# design.net
KiCad netlist of a schematic drawn in Altium Designer
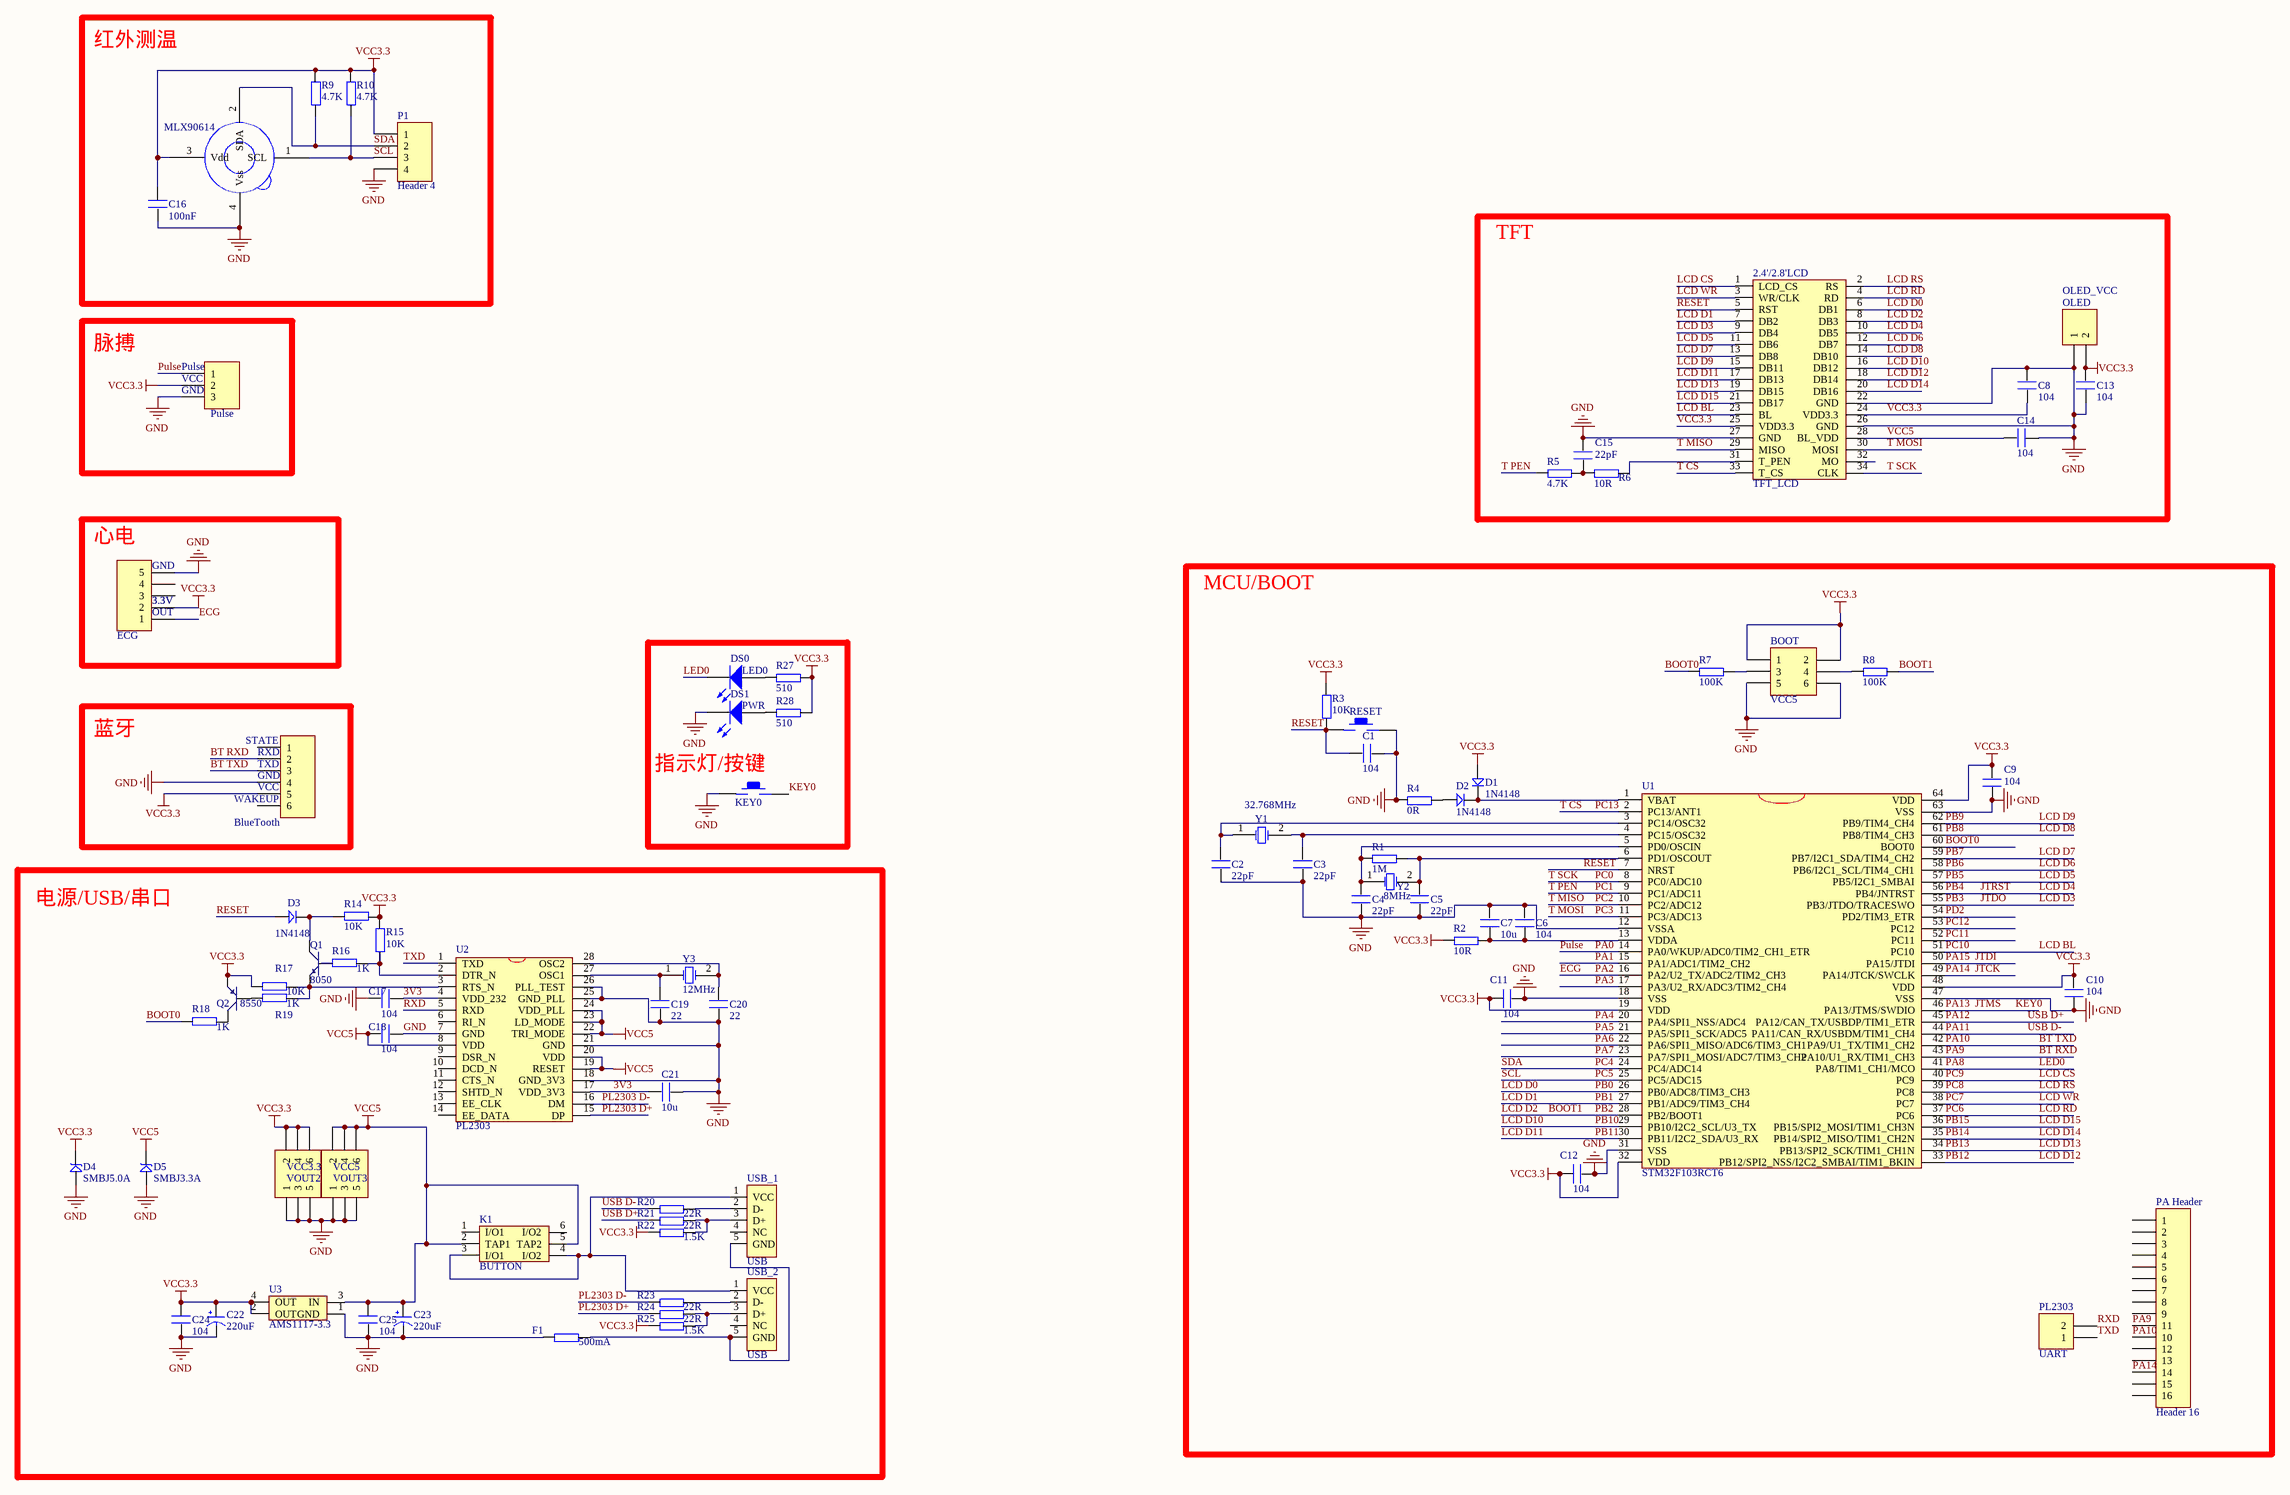
[diagram p0: 远程医疗.SchDoc]

(export (version "E")
  (design (tool "Eeschema 10.0.6"))
  (components
    (comp (ref "2.4'/2.8'LCD")
      (value "TFT_LCD")
      (footprint "DB2*17")
      (libsource (lib "MiniSTM32 V2.0封装库") (part "TFT_LCD"))
    )
    (comp (ref "BlueTooth")
      (value "BlueTooth")
      (footprint "BlueTooth")
      (libsource (lib "my Integrated lib ") (part "BlueTooth"))
    )
    (comp (ref "BOOT")
      (value "VCC5")
      (footprint "HDR2X3")
      (description "Header, 3-Pin, Dual row")
      (fields (field (name "PUBLISHER") "Altium Limited"))
      (libsource (lib "") (part "Header 3X2_1"))
    )
    (comp (ref "C1") (value "104") (footprint "0603P") (libsource (lib "MiniSTM32 V2.0封装库") (part "C")))
    (comp (ref "C2") (value "22pF") (footprint "0603P") (libsource (lib "MiniSTM32 V2.0封装库") (part "C")))
    (comp (ref "C3") (value "22pF") (footprint "0603P") (libsource (lib "MiniSTM32 V2.0封装库") (part "C")))
    (comp (ref "C4") (value "22pF") (footprint "0603P") (libsource (lib "MiniSTM32 V2.0封装库") (part "C")))
    (comp (ref "C5") (value "22pF") (footprint "0603P") (libsource (lib "MiniSTM32 V2.0封装库") (part "C")))
    (comp (ref "C6") (value "104") (footprint "0603P") (libsource (lib "MiniSTM32 V2.0封装库") (part "C")))
    (comp (ref "C7") (value "10u") (footprint "0603P") (libsource (lib "MiniSTM32 V2.0封装库") (part "C")))
    (comp (ref "C8") (value "104") (footprint "0603P") (libsource (lib "MiniSTM32 V2.0封装库") (part "C")))
    (comp (ref "C9") (value "104") (footprint "0603P") (libsource (lib "MiniSTM32 V2.0封装库") (part "C")))
    (comp (ref "C10") (value "104") (footprint "0603P") (libsource (lib "MiniSTM32 V2.0封装库") (part "C")))
    (comp (ref "C11") (value "104") (footprint "0603P") (libsource (lib "MiniSTM32 V2.0封装库") (part "C")))
    (comp (ref "C12") (value "104") (footprint "0603P") (libsource (lib "MiniSTM32 V2.0封装库") (part "C")))
    (comp (ref "C13") (value "104") (footprint "0603P") (libsource (lib "MiniSTM32 V2.0封装库") (part "C")))
    (comp (ref "C14") (value "104") (footprint "0603P") (libsource (lib "MiniSTM32 V2.0封装库") (part "C")))
    (comp (ref "C15") (value "22pF") (footprint "0603P") (libsource (lib "MiniSTM32 V2.0封装库") (part "C")))
    (comp (ref "C16") (value "100nF") (footprint "0603P") (libsource (lib "MiniSTM32 V2.0封装库") (part "C")))
    (comp (ref "C17") (value "104") (footprint "0603P") (libsource (lib "MiniSTM32 V2.0封装库") (part "C")))
    (comp (ref "C18") (value "104") (footprint "0603P") (libsource (lib "MiniSTM32 V2.0封装库") (part "C")))
    (comp (ref "C19") (value "22") (footprint "0603P") (libsource (lib "MiniSTM32 V2.0封装库") (part "C")))
    (comp (ref "C20") (value "22") (footprint "0603P") (libsource (lib "MiniSTM32 V2.0封装库") (part "C")))
    (comp (ref "C21") (value "10u") (footprint "0603P") (libsource (lib "MiniSTM32 V2.0封装库") (part "C")))
    (comp (ref "C22")
      (value "220uF")
      (footprint "CC6.56.5")
      (libsource (lib "MiniSTM32 V2.0封装库") (part "CAP"))
    )
    (comp (ref "C23")
      (value "220uF")
      (footprint "CC6.56.5")
      (libsource (lib "MiniSTM32 V2.0封装库") (part "CAP"))
    )
    (comp (ref "C24") (value "104") (footprint "0603P") (libsource (lib "MiniSTM32 V2.0封装库") (part "C")))
    (comp (ref "C25") (value "104") (footprint "0603P") (libsource (lib "MiniSTM32 V2.0封装库") (part "C")))
    (comp (ref "D1")
      (value "1N4148")
      (footprint "DIODE_SOP")
      (libsource (lib "MiniSTM32 V2.0封装库") (part "D"))
    )
    (comp (ref "D2")
      (value "1N4148")
      (footprint "DIODE_SOP")
      (libsource (lib "MiniSTM32 V2.0封装库") (part "D"))
    )
    (comp (ref "D3")
      (value "1N4148")
      (footprint "DIODE_SOP")
      (libsource (lib "MiniSTM32 V2.0封装库") (part "D"))
    )
    (comp (ref "D4")
      (value "SMBJ5.0A")
      (footprint "SMBJ")
      (description "TVS")
      (libsource (lib "MiniSTM32 V2.0封装库") (part "SMBJ"))
    )
    (comp (ref "D5")
      (value "SMBJ3.3A")
      (footprint "SMBJ")
      (description "TVS")
      (libsource (lib "MiniSTM32 V2.0封装库") (part "SMBJ"))
    )
    (comp (ref "DS0")
      (value "LED0")
      (footprint "SMDLED")
      (description "Typical RED, GREEN, YELLOW, AMBER GaAs LED")
      (fields (field (name "PUBLISHER") "Altium Limited"))
      (libsource (lib "MiniSTM32 V2.0封装库") (part "LED2"))
    )
    (comp (ref "DS1")
      (value "PWR")
      (footprint "SMDLED")
      (description "Typical RED, GREEN, YELLOW, AMBER GaAs LED")
      (fields (field (name "PUBLISHER") "Altium Limited"))
      (libsource (lib "MiniSTM32 V2.0封装库") (part "LED2"))
    )
    (comp (ref "ECG") (value "ECG") (footprint "ECG") (libsource (lib "my Integrated lib ") (part "ECG")))
    (comp (ref "F1") (value "500mA") (footprint "0603P") (libsource (lib "MiniSTM32 V2.0封装库") (part "R")))
    (comp (ref "K1")
      (value "BUTTON")
      (footprint "BTN8.5*8.5")
      (libsource (lib "MiniSTM32 V2.0封装库") (part "BUTTON"))
    )
    (comp (ref "KEY0")
      (value "KEY_M")
      (footprint "KEY_M")
      (libsource (lib "MiniSTM32 V2.0封装库") (part "KEY_M"))
    )
    (comp (ref "MLX90614")
      (value "MLX90614")
      (footprint "MLX90614")
      (libsource (lib "my Integrated lib ") (part "MLX90614"))
    )
    (comp (ref "OLED")
      (value "OLED_VCC")
      (footprint "HDR1X2")
      (description "Header, 2-Pin")
      (fields (field (name "PUBLISHER") "Altium Limited"))
      (libsource (lib "") (part "Header 2_1"))
    )
    (comp (ref "P1")
      (value "Header 4")
      (footprint "HDR1X4")
      (description "Header, 4-Pin")
      (fields (field (name "PUBLISHER") "Altium Limited"))
      (libsource (lib "Miscellaneous Connectors") (part "Header 4"))
    )
    (comp (ref "PA Header")
      (value "Header 16")
      (footprint "HDR1X16")
      (description "Header, 16-Pin")
      (fields (field (name "PUBLISHER") "Altium Limited"))
      (libsource (lib "MiniSTM32 V2.0封装库") (part "Header 16"))
    )
    (comp (ref "PL2303")
      (value "UART")
      (footprint "HDR1X2")
      (description "Header, 2-Pin")
      (fields (field (name "PUBLISHER") "Altium Limited"))
      (libsource (lib "MiniSTM32 V2.0封装库") (part "Header 2"))
    )
    (comp (ref "Pulse")
      (value "Pulse")
      (footprint "Pulse")
      (libsource (lib "my Integrated lib ") (part "Pulse"))
    )
    (comp (ref "Q1")
      (value "8050")
      (footprint "SOT-23R")
      (description "8050/BCW846/BCW847")
      (libsource (lib "MiniSTM32 V2.0封装库") (part "NPN"))
    )
    (comp (ref "Q2")
      (value "8550")
      (footprint "SOT-23R")
      (description "8550/BCW68")
      (libsource (lib "MiniSTM32 V2.0封装库") (part "PNP"))
    )
    (comp (ref "R1") (value "1M") (footprint "0603P") (libsource (lib "MiniSTM32 V2.0封装库") (part "R")))
    (comp (ref "R2") (value "10R") (footprint "0603P") (libsource (lib "MiniSTM32 V2.0封装库") (part "R")))
    (comp (ref "R3") (value "10K") (footprint "0603P") (libsource (lib "MiniSTM32 V2.0封装库") (part "R")))
    (comp (ref "R4") (value "0R") (footprint "0603P") (libsource (lib "MiniSTM32 V2.0封装库") (part "R")))
    (comp (ref "R5") (value "4.7K") (footprint "0603P") (libsource (lib "MiniSTM32 V2.0封装库") (part "R")))
    (comp (ref "R6") (value "10R") (footprint "0603P") (libsource (lib "MiniSTM32 V2.0封装库") (part "R")))
    (comp (ref "R7") (value "100K") (footprint "0603P") (libsource (lib "MiniSTM32 V2.0封装库") (part "R")))
    (comp (ref "R8") (value "100K") (footprint "0603P") (libsource (lib "MiniSTM32 V2.0封装库") (part "R")))
    (comp (ref "R9") (value "4.7K") (footprint "0603P") (libsource (lib "MiniSTM32 V2.0封装库") (part "R")))
    (comp (ref "R10") (value "4.7K") (footprint "0603P") (libsource (lib "MiniSTM32 V2.0封装库") (part "R")))
    (comp (ref "R14") (value "10K") (footprint "0603P") (libsource (lib "MiniSTM32 V2.0封装库") (part "R")))
    (comp (ref "R15") (value "10K") (footprint "0603P") (libsource (lib "MiniSTM32 V2.0封装库") (part "R")))
    (comp (ref "R16") (value "1K") (footprint "0603P") (libsource (lib "MiniSTM32 V2.0封装库") (part "R")))
    (comp (ref "R17") (value "10K") (footprint "0603P") (libsource (lib "MiniSTM32 V2.0封装库") (part "R")))
    (comp (ref "R18") (value "1K") (footprint "0603P") (libsource (lib "MiniSTM32 V2.0封装库") (part "R")))
    (comp (ref "R19") (value "1K") (footprint "0603P") (libsource (lib "MiniSTM32 V2.0封装库") (part "R")))
    (comp (ref "R20") (value "22R") (footprint "0603P") (libsource (lib "MiniSTM32 V2.0封装库") (part "R")))
    (comp (ref "R21") (value "22R") (footprint "0603P") (libsource (lib "MiniSTM32 V2.0封装库") (part "R")))
    (comp (ref "R22") (value "1.5K") (footprint "0603P") (libsource (lib "MiniSTM32 V2.0封装库") (part "R")))
    (comp (ref "R23") (value "22R") (footprint "0603P") (libsource (lib "MiniSTM32 V2.0封装库") (part "R")))
    (comp (ref "R24") (value "22R") (footprint "0603P") (libsource (lib "MiniSTM32 V2.0封装库") (part "R")))
    (comp (ref "R25") (value "1.5K") (footprint "0603P") (libsource (lib "MiniSTM32 V2.0封装库") (part "R")))
    (comp (ref "R27") (value "510") (footprint "0603P") (libsource (lib "MiniSTM32 V2.0封装库") (part "R")))
    (comp (ref "R28") (value "510") (footprint "0603P") (libsource (lib "MiniSTM32 V2.0封装库") (part "R")))
    (comp (ref "RESET")
      (value "KEY_M")
      (footprint "KEY_M")
      (libsource (lib "MiniSTM32 V2.0封装库") (part "KEY_M"))
    )
    (comp (ref "U1")
      (value "STM32F103RCT6")
      (footprint "LQFP64")
      (libsource (lib "MiniSTM32 V2.0封装库") (part "STM32F103RBT6"))
    )
    (comp (ref "U2")
      (value "PL2303")
      (footprint "ssop28")
      (libsource (lib "MiniSTM32 V2.0封装库") (part "PL2303"))
    )
    (comp (ref "U3")
      (value "AMS1117-3.3")
      (footprint "AMS1117")
      (libsource (lib "MiniSTM32 V2.0封装库") (part "AMS1117"))
    )
    (comp (ref "USB_1")
      (value "USB")
      (footprint "USB/SM0.8-6H5")
      (libsource (lib "MiniSTM32 V2.0封装库") (part "USB5"))
    )
    (comp (ref "USB_2")
      (value "USB")
      (footprint "USB/SM0.8-6H5")
      (libsource (lib "MiniSTM32 V2.0封装库") (part "USB5"))
    )
    (comp (ref "VOUT2")
      (value "VCC3.3")
      (footprint "HDR2X3")
      (description "Header, 3-Pin, Dual row")
      (fields (field (name "PUBLISHER") "Altium Limited"))
      (libsource (lib "MiniSTM32 V2.0封装库") (part "Header 3X2"))
    )
    (comp (ref "VOUT3")
      (value "VCC5")
      (footprint "HDR2X3")
      (description "Header, 3-Pin, Dual row")
      (fields (field (name "PUBLISHER") "Altium Limited"))
      (libsource (lib "MiniSTM32 V2.0封装库") (part "Header 3X2"))
    )
    (comp (ref "Y1")
      (value "32.768MHz")
      (footprint "XTAL 32M")
      (description "Crystal Oscillator")
      (fields (field (name "PUBLISHER") "Altium Limited"))
      (libsource (lib "MiniSTM32 V2.0封装库") (part "XTAL"))
    )
    (comp (ref "Y2")
      (value "8MHz")
      (footprint "XTAL_US")
      (description "Crystal Oscillator")
      (fields (field (name "PUBLISHER") "Altium Limited"))
      (libsource (lib "MiniSTM32 V2.0封装库") (part "XTAL"))
    )
    (comp (ref "Y3")
      (value "12MHz")
      (footprint "XTAL_US")
      (description "Crystal Oscillator")
      (fields (field (name "PUBLISHER") "Altium Limited"))
      (libsource (lib "MiniSTM32 V2.0封装库") (part "XTAL"))
    )
  )
  (nets
    (net (code "1") (name "/3V3") (class "Default")
      (node (ref "C17") (pin "2") (pintype "passive"))
      (node (ref "C21") (pin "2") (pintype "passive"))
      (node (ref "U2") (pin "17") (pinfunction "VDD_3V3_17") (pintype "passive"))
      (node (ref "U2") (pin "4") (pinfunction "VDD_232_4") (pintype "passive"))
    )
    (net (code "2") (name "/BOOT0") (class "Default")
      (node (ref "R18") (pin "2") (pintype "passive"))
      (node (ref "R7") (pin "1") (pintype "passive"))
      (node (ref "U1") (pin "60") (pinfunction "BOOT0_60") (pintype "passive"))
    )
    (net (code "3") (name "/BOOT1") (class "Default")
      (node (ref "2.4'/2.8'LCD") (pin "8") (pinfunction "DB3_8") (pintype "passive"))
      (node (ref "R8") (pin "2") (pintype "passive"))
      (node (ref "U1") (pin "28") (pinfunction "PB2/BOOT1_28") (pintype "passive"))
    )
    (net (code "4") (name "/BT RXD") (class "Default")
      (node (ref "BlueTooth") (pin "2") (pinfunction "2_2") (pintype "passive"))
      (node (ref "PA Header") (pin "11") (pinfunction "11_11") (pintype "passive"))
      (node (ref "U1") (pin "43") (pinfunction "PA10/U1_RX/TIM1_CH3_43") (pintype "passive"))
    )
    (net (code "5") (name "/BT TXD") (class "Default")
      (node (ref "BlueTooth") (pin "3") (pinfunction "3_3") (pintype "passive"))
      (node (ref "PA Header") (pin "10") (pinfunction "10_10") (pintype "passive"))
      (node (ref "U1") (pin "42") (pinfunction "PA9/U1_TX/TIM1_CH2_42") (pintype "passive"))
    )
    (net (code "6") (name "/ECG") (class "Default")
      (node (ref "ECG") (pin "1") (pinfunction "1_1") (pintype "passive"))
      (node (ref "U1") (pin "16") (pinfunction "PA2/U2_TX/ADC2/TIM2_CH3_16") (pintype "passive"))
    )
    (net (code "7") (name "/JTCK") (class "Default")
      (node (ref "PA Header") (pin "14") (pinfunction "14_14") (pintype "passive"))
      (node (ref "U1") (pin "49") (pinfunction "PA14/JTCK/SWCLK_49") (pintype "passive"))
    )
    (net (code "8") (name "/JTDI") (class "Default")
      (node (ref "U1") (pin "50") (pinfunction "PA15/JTDI_50") (pintype "passive"))
    )
    (net (code "9") (name "/JTDO") (class "Default")
      (node (ref "2.4'/2.8'LCD") (pin "9") (pinfunction "DB4_9") (pintype "passive"))
      (node (ref "U1") (pin "55") (pinfunction "PB3/JTDO/TRACESWO_55") (pintype "passive"))
    )
    (net (code "10") (name "/JTMS") (class "Default")
      (node (ref "KEY0") (pin "2") (pinfunction "2_2") (pintype "passive"))
      (node (ref "U1") (pin "46") (pinfunction "PA13/JTMS/SWDIO_46") (pintype "passive"))
    )
    (net (code "11") (name "/JTRST") (class "Default")
      (node (ref "2.4'/2.8'LCD") (pin "10") (pinfunction "DB5_10") (pintype "passive"))
      (node (ref "U1") (pin "56") (pinfunction "PB4/JNTRST_56") (pintype "passive"))
    )
    (net (code "12") (name "/LCD BL") (class "Default")
      (node (ref "2.4'/2.8'LCD") (pin "23") (pinfunction "BL_23") (pintype "passive"))
      (node (ref "U1") (pin "51") (pinfunction "PC10_51") (pintype "passive"))
    )
    (net (code "13") (name "/LCD CS") (class "Default")
      (node (ref "2.4'/2.8'LCD") (pin "1") (pinfunction "LCD_CS_1") (pintype "passive"))
      (node (ref "U1") (pin "40") (pinfunction "PC9_40") (pintype "passive"))
    )
    (net (code "14") (name "/LCD D0") (class "Default")
      (node (ref "2.4'/2.8'LCD") (pin "6") (pinfunction "DB1_6") (pintype "passive"))
      (node (ref "U1") (pin "26") (pinfunction "PB0/ADC8/TIM3_CH3_26") (pintype "passive"))
    )
    (net (code "15") (name "/LCD D1") (class "Default")
      (node (ref "2.4'/2.8'LCD") (pin "7") (pinfunction "DB2_7") (pintype "passive"))
      (node (ref "U1") (pin "27") (pinfunction "PB1/ADC9/TIM3_CH4_27") (pintype "passive"))
    )
    (net (code "16") (name "/LCD D5") (class "Default")
      (node (ref "2.4'/2.8'LCD") (pin "11") (pinfunction "DB6_11") (pintype "passive"))
      (node (ref "U1") (pin "57") (pinfunction "PB5/I2C1_SMBAI_57") (pintype "passive"))
    )
    (net (code "17") (name "/LCD D6") (class "Default")
      (node (ref "2.4'/2.8'LCD") (pin "12") (pinfunction "DB7_12") (pintype "passive"))
      (node (ref "U1") (pin "58") (pinfunction "PB6/I2C1_SCL/TIM4_CH1_58") (pintype "passive"))
    )
    (net (code "18") (name "/LCD D7") (class "Default")
      (node (ref "2.4'/2.8'LCD") (pin "13") (pinfunction "DB8_13") (pintype "passive"))
      (node (ref "U1") (pin "59") (pinfunction "PB7/I2C1_SDA/TIM4_CH2_59") (pintype "passive"))
    )
    (net (code "19") (name "/LCD D8") (class "Default")
      (node (ref "2.4'/2.8'LCD") (pin "14") (pinfunction "DB10_14") (pintype "passive"))
      (node (ref "U1") (pin "61") (pinfunction "PB8/TIM4_CH3_61") (pintype "passive"))
    )
    (net (code "20") (name "/LCD D9") (class "Default")
      (node (ref "2.4'/2.8'LCD") (pin "15") (pinfunction "DB11_15") (pintype "passive"))
      (node (ref "U1") (pin "62") (pinfunction "PB9/TIM4_CH4_62") (pintype "passive"))
    )
    (net (code "21") (name "/LCD D10") (class "Default")
      (node (ref "2.4'/2.8'LCD") (pin "16") (pinfunction "DB12_16") (pintype "passive"))
      (node (ref "U1") (pin "29") (pinfunction "PB10/I2C2_SCL/U3_TX_29") (pintype "passive"))
    )
    (net (code "22") (name "/LCD D11") (class "Default")
      (node (ref "2.4'/2.8'LCD") (pin "17") (pinfunction "DB13_17") (pintype "passive"))
      (node (ref "U1") (pin "30") (pinfunction "PB11/I2C2_SDA/U3_RX_30") (pintype "passive"))
    )
    (net (code "23") (name "/LCD D12") (class "Default")
      (node (ref "2.4'/2.8'LCD") (pin "18") (pinfunction "DB14_18") (pintype "passive"))
      (node (ref "U1") (pin "33") (pinfunction "PB12/SPI2_NSS/I2C2_SMBAI/TIM1_BKIN_33") (pintype "passive"))
    )
    (net (code "24") (name "/LCD D13") (class "Default")
      (node (ref "2.4'/2.8'LCD") (pin "19") (pinfunction "DB15_19") (pintype "passive"))
      (node (ref "U1") (pin "34") (pinfunction "PB13/SPI2_SCK/TIM1_CH1N_34") (pintype "passive"))
    )
    (net (code "25") (name "/LCD D14") (class "Default")
      (node (ref "2.4'/2.8'LCD") (pin "20") (pinfunction "DB16_20") (pintype "passive"))
      (node (ref "U1") (pin "35") (pinfunction "PB14/SPI2_MISO/TIM1_CH2N_35") (pintype "passive"))
    )
    (net (code "26") (name "/LCD D15") (class "Default")
      (node (ref "2.4'/2.8'LCD") (pin "21") (pinfunction "DB17_21") (pintype "passive"))
      (node (ref "U1") (pin "36") (pinfunction "PB15/SPI2_MOSI/TIM1_CH3N_36") (pintype "passive"))
    )
    (net (code "27") (name "/LCD RD") (class "Default")
      (node (ref "2.4'/2.8'LCD") (pin "4") (pinfunction "RD_4") (pintype "passive"))
      (node (ref "U1") (pin "37") (pinfunction "PC6_37") (pintype "passive"))
    )
    (net (code "28") (name "/LCD RS") (class "Default")
      (node (ref "2.4'/2.8'LCD") (pin "2") (pinfunction "RS_2") (pintype "passive"))
      (node (ref "U1") (pin "39") (pinfunction "PC8_39") (pintype "passive"))
    )
    (net (code "29") (name "/LCD WR") (class "Default")
      (node (ref "2.4'/2.8'LCD") (pin "3") (pinfunction "WR/CLK_3") (pintype "passive"))
      (node (ref "U1") (pin "38") (pinfunction "PC7_38") (pintype "passive"))
    )
    (net (code "30") (name "/LED0") (class "Default")
      (node (ref "DS0") (pin "2") (pinfunction "K_2") (pintype "passive"))
      (node (ref "U1") (pin "41") (pinfunction "PA8/TIM1_CH1/MCO_41") (pintype "passive"))
    )
    (net (code "31") (name "/PA0") (class "Default")
      (node (ref "Pulse") (pin "1") (pinfunction "1_1") (pintype "passive"))
      (node (ref "U1") (pin "14") (pinfunction "PA0/WKUP/ADC0/TIM2_CH1_ETR_14") (pintype "passive"))
    )
    (net (code "32") (name "/PA1") (class "Default")
      (node (ref "U1") (pin "15") (pinfunction "PA1/ADC1/TIM2_CH2_15") (pintype "passive"))
    )
    (net (code "33") (name "/PA3") (class "Default")
      (node (ref "U1") (pin "17") (pinfunction "PA3/U2_RX/ADC3/TIM2_CH4_17") (pintype "passive"))
    )
    (net (code "34") (name "/PA4") (class "Default")
      (node (ref "U1") (pin "20") (pinfunction "PA4/SPI1_NSS/ADC4_20") (pintype "passive"))
    )
    (net (code "35") (name "/PA5") (class "Default")
      (node (ref "U1") (pin "21") (pinfunction "PA5/SPI1_SCK/ADC5_21") (pintype "passive"))
    )
    (net (code "36") (name "/PA6") (class "Default")
      (node (ref "U1") (pin "22") (pinfunction "PA6/SPI1_MISO/ADC6/TIM3_CH1_22") (pintype "passive"))
    )
    (net (code "37") (name "/PA7") (class "Default")
      (node (ref "U1") (pin "23") (pinfunction "PA7/SPI1_MOSI/ADC7/TIM3_CH2_23") (pintype "passive"))
    )
    (net (code "38") (name "/PA11") (class "Default")
      (node (ref "R20") (pin "1") (pintype "passive"))
      (node (ref "U1") (pin "44") (pinfunction "PA11/CAN_RX/USBDM/TIM1_CH4_44") (pintype "passive"))
    )
    (net (code "39") (name "/PA12") (class "Default")
      (node (ref "R21") (pin "1") (pintype "passive"))
      (node (ref "U1") (pin "45") (pinfunction "PA12/CAN_TX/USBDP/TIM1_ETR_45") (pintype "passive"))
    )
    (net (code "40") (name "/PC0") (class "Default")
      (node (ref "2.4'/2.8'LCD") (pin "34") (pinfunction "CLK_34") (pintype "passive"))
      (node (ref "U1") (pin "8") (pinfunction "PC0/ADC10_8") (pintype "passive"))
    )
    (net (code "41") (name "/PC1") (class "Default")
      (node (ref "R5") (pin "1") (pintype "passive"))
      (node (ref "U1") (pin "9") (pinfunction "PC1/ADC11_9") (pintype "passive"))
    )
    (net (code "42") (name "/PC2") (class "Default")
      (node (ref "2.4'/2.8'LCD") (pin "29") (pinfunction "MISO_29") (pintype "passive"))
      (node (ref "U1") (pin "10") (pinfunction "PC2/ADC12_10") (pintype "passive"))
    )
    (net (code "43") (name "/PC3") (class "Default")
      (node (ref "2.4'/2.8'LCD") (pin "30") (pinfunction "MOSI_30") (pintype "passive"))
      (node (ref "U1") (pin "11") (pinfunction "PC3/ADC13_11") (pintype "passive"))
    )
    (net (code "44") (name "/PC4") (class "Default")
      (node (ref "MLX90614") (pin "2") (pinfunction "SDA_2") (pintype "passive"))
      (node (ref "P1") (pin "2") (pinfunction "2_2") (pintype "passive"))
      (node (ref "R9") (pin "1") (pintype "passive"))
      (node (ref "U1") (pin "24") (pinfunction "PC4/ADC14_24") (pintype "passive"))
    )
    (net (code "45") (name "/PC5") (class "Default")
      (node (ref "MLX90614") (pin "1") (pinfunction "SCL_1") (pintype "passive"))
      (node (ref "P1") (pin "3") (pinfunction "3_3") (pintype "passive"))
      (node (ref "R10") (pin "1") (pintype "passive"))
      (node (ref "U1") (pin "25") (pinfunction "PC5/ADC15_25") (pintype "passive"))
    )
    (net (code "46") (name "/PC11") (class "Default")
      (node (ref "U1") (pin "52") (pinfunction "PC11_52") (pintype "passive"))
    )
    (net (code "47") (name "/PC12") (class "Default")
      (node (ref "U1") (pin "53") (pinfunction "PC12_53") (pintype "passive"))
    )
    (net (code "48") (name "/PC13") (class "Default")
      (node (ref "2.4'/2.8'LCD") (pin "33") (pinfunction "T_CS_33") (pintype "passive"))
      (node (ref "U1") (pin "2") (pinfunction "PC13/ANT1_2") (pintype "passive"))
    )
    (net (code "49") (name "/PD2") (class "Default")
      (node (ref "U1") (pin "54") (pinfunction "PD2/TIM3_ETR_54") (pintype "passive"))
    )
    (net (code "50") (name "/PL2303 D+") (class "Default")
      (node (ref "R24") (pin "1") (pintype "passive"))
      (node (ref "U2") (pin "15") (pinfunction "DP_15") (pintype "passive"))
    )
    (net (code "51") (name "/PL2303 D-") (class "Default")
      (node (ref "R23") (pin "1") (pintype "passive"))
      (node (ref "U2") (pin "16") (pinfunction "DM_16") (pintype "passive"))
    )
    (net (code "52") (name "/RESET") (class "Default")
      (node (ref "2.4'/2.8'LCD") (pin "5") (pinfunction "RST_5") (pintype "passive"))
      (node (ref "C1") (pin "2") (pintype "passive"))
      (node (ref "D3") (pin "1") (pintype "passive"))
      (node (ref "R3") (pin "1") (pintype "passive"))
      (node (ref "RESET") (pin "1") (pinfunction "1_1") (pintype "passive"))
      (node (ref "U1") (pin "7") (pinfunction "NRST_7") (pintype "passive"))
    )
    (net (code "53") (name "/RXD") (class "Default")
      (node (ref "PL2303") (pin "2") (pinfunction "2_2") (pintype "passive"))
      (node (ref "U2") (pin "5") (pinfunction "RXD_5") (pintype "passive"))
    )
    (net (code "54") (name "/TXD") (class "Default")
      (node (ref "PL2303") (pin "1") (pinfunction "1_1") (pintype "passive"))
      (node (ref "U2") (pin "1") (pinfunction "TXD_1") (pintype "passive"))
    )
    (net (code "55") (name "GND") (class "Default")
      (node (ref "2.4'/2.8'LCD") (pin "22") (pinfunction "GND_22") (pintype "passive"))
      (node (ref "2.4'/2.8'LCD") (pin "26") (pinfunction "GND_26") (pintype "passive"))
      (node (ref "2.4'/2.8'LCD") (pin "27") (pinfunction "GND_27") (pintype "passive"))
      (node (ref "BOOT") (pin "5") (pinfunction "5_5") (pintype "passive"))
      (node (ref "BOOT") (pin "6") (pinfunction "6_6") (pintype "passive"))
      (node (ref "BlueTooth") (pin "4") (pinfunction "4_4") (pintype "passive"))
      (node (ref "C1") (pin "1") (pintype "passive"))
      (node (ref "C10") (pin "2") (pintype "passive"))
      (node (ref "C11") (pin "2") (pintype "passive"))
      (node (ref "C12") (pin "2") (pintype "passive"))
      (node (ref "C13") (pin "1") (pintype "passive"))
      (node (ref "C14") (pin "1") (pintype "passive"))
      (node (ref "C15") (pin "2") (pintype "passive"))
      (node (ref "C16") (pin "1") (pintype "passive"))
      (node (ref "C17") (pin "1") (pintype "passive"))
      (node (ref "C18") (pin "2") (pintype "passive"))
      (node (ref "C19") (pin "1") (pintype "passive"))
      (node (ref "C2") (pin "1") (pintype "passive"))
      (node (ref "C20") (pin "1") (pintype "passive"))
      (node (ref "C21") (pin "1") (pintype "passive"))
      (node (ref "C22") (pin "2") (pinfunction "GND_2") (pintype "passive"))
      (node (ref "C23") (pin "2") (pinfunction "GND_2") (pintype "passive"))
      (node (ref "C24") (pin "1") (pintype "passive"))
      (node (ref "C25") (pin "1") (pintype "passive"))
      (node (ref "C3") (pin "1") (pintype "passive"))
      (node (ref "C4") (pin "1") (pintype "passive"))
      (node (ref "C5") (pin "1") (pintype "passive"))
      (node (ref "C6") (pin "1") (pintype "passive"))
      (node (ref "C7") (pin "1") (pintype "passive"))
      (node (ref "C8") (pin "2") (pintype "passive"))
      (node (ref "C9") (pin "2") (pintype "passive"))
      (node (ref "D4") (pin "1") (pintype "passive"))
      (node (ref "D5") (pin "1") (pintype "passive"))
      (node (ref "DS1") (pin "2") (pinfunction "K_2") (pintype "passive"))
      (node (ref "ECG") (pin "5") (pinfunction "5_5") (pintype "passive"))
      (node (ref "F1") (pin "1") (pintype "passive"))
      (node (ref "KEY0") (pin "1") (pinfunction "1_1") (pintype "passive"))
      (node (ref "MLX90614") (pin "4") (pinfunction "Vss_4") (pintype "passive"))
      (node (ref "OLED") (pin "1") (pinfunction "1_1") (pintype "passive"))
      (node (ref "P1") (pin "4") (pinfunction "4_4") (pintype "passive"))
      (node (ref "Pulse") (pin "3") (pinfunction "3_3") (pintype "passive"))
      (node (ref "R4") (pin "1") (pintype "passive"))
      (node (ref "RESET") (pin "2") (pinfunction "2_2") (pintype "passive"))
      (node (ref "U1") (pin "12") (pinfunction "VSSA_12") (pintype "passive"))
      (node (ref "U1") (pin "18") (pinfunction "VSS_18") (pintype "passive"))
      (node (ref "U1") (pin "31") (pinfunction "VSS_31") (pintype "passive"))
      (node (ref "U1") (pin "47") (pinfunction "VSS_47") (pintype "passive"))
      (node (ref "U1") (pin "63") (pinfunction "VSS_63") (pintype "passive"))
      (node (ref "U2") (pin "18") (pinfunction "GND_3V3_18") (pintype "passive"))
      (node (ref "U2") (pin "21") (pinfunction "GND_21") (pintype "passive"))
      (node (ref "U2") (pin "25") (pinfunction "GND_PLL_25") (pintype "passive"))
      (node (ref "U2") (pin "26") (pinfunction "PLL_TEST_26") (pintype "passive"))
      (node (ref "U2") (pin "7") (pinfunction "GND_7") (pintype "passive"))
      (node (ref "U3") (pin "1") (pinfunction "GND_1") (pintype "passive"))
      (node (ref "VOUT2") (pin "1") (pinfunction "1_1") (pintype "passive"))
      (node (ref "VOUT2") (pin "3") (pinfunction "3_3") (pintype "passive"))
      (node (ref "VOUT2") (pin "5") (pinfunction "5_5") (pintype "passive"))
      (node (ref "VOUT3") (pin "1") (pinfunction "1_1") (pintype "passive"))
      (node (ref "VOUT3") (pin "3") (pinfunction "3_3") (pintype "passive"))
      (node (ref "VOUT3") (pin "5") (pinfunction "5_5") (pintype "passive"))
    )
    (net (code "56") (name "Net-(2.4'/2.8'LCD-T_PEN)") (class "Default")
      (node (ref "2.4'/2.8'LCD") (pin "31") (pinfunction "T_PEN_31") (pintype "passive"))
      (node (ref "R6") (pin "2") (pintype "passive"))
    )
    (net (code "57") (name "Net-(BOOT-Pad3)") (class "Default")
      (node (ref "BOOT") (pin "3") (pinfunction "3_3") (pintype "passive"))
      (node (ref "R7") (pin "2") (pintype "passive"))
    )
    (net (code "58") (name "Net-(BOOT-Pad4)") (class "Default")
      (node (ref "BOOT") (pin "4") (pinfunction "4_4") (pintype "passive"))
      (node (ref "R8") (pin "1") (pintype "passive"))
    )
    (net (code "59") (name "Net-(C15-Pad1)") (class "Default")
      (node (ref "C15") (pin "1") (pintype "passive"))
      (node (ref "R5") (pin "2") (pintype "passive"))
      (node (ref "R6") (pin "1") (pintype "passive"))
    )
    (net (code "60") (name "Net-(D2-Pad1)") (class "Default")
      (node (ref "D2") (pin "1") (pintype "passive"))
      (node (ref "R4") (pin "2") (pintype "passive"))
    )
    (net (code "61") (name "Net-(DS0-A)") (class "Default")
      (node (ref "DS0") (pin "1") (pinfunction "A_1") (pintype "passive"))
      (node (ref "R27") (pin "1") (pintype "passive"))
    )
    (net (code "62") (name "Net-(DS1-A)") (class "Default")
      (node (ref "DS1") (pin "1") (pinfunction "A_1") (pintype "passive"))
      (node (ref "R28") (pin "1") (pintype "passive"))
    )
    (net (code "63") (name "Net-(Q1-B)") (class "Default")
      (node (ref "Q1") (pin "2") (pinfunction "B_2") (pintype "passive"))
      (node (ref "R16") (pin "2") (pintype "passive"))
    )
    (net (code "64") (name "Net-(Q1-C)") (class "Default")
      (node (ref "D3") (pin "2") (pintype "passive"))
      (node (ref "Q1") (pin "3") (pinfunction "C_3") (pintype "passive"))
      (node (ref "R14") (pin "2") (pintype "passive"))
    )
    (net (code "65") (name "Net-(Q1-E)") (class "Default")
      (node (ref "Q1") (pin "1") (pinfunction "E_1") (pintype "passive"))
      (node (ref "R17") (pin "1") (pintype "passive"))
      (node (ref "R19") (pin "1") (pintype "passive"))
      (node (ref "U2") (pin "3") (pinfunction "RTS_N_3") (pintype "passive"))
    )
    (net (code "66") (name "Net-(Q2-B)") (class "Default")
      (node (ref "Q2") (pin "2") (pinfunction "B_2") (pintype "passive"))
      (node (ref "R19") (pin "2") (pintype "passive"))
    )
    (net (code "67") (name "Net-(Q2-C)") (class "Default")
      (node (ref "Q2") (pin "3") (pinfunction "C_3") (pintype "passive"))
      (node (ref "R18") (pin "1") (pintype "passive"))
    )
    (net (code "68") (name "Net-(U1-PC14{slash}OSC32)") (class "Default")
      (node (ref "C2") (pin "2") (pintype "passive"))
      (node (ref "U1") (pin "3") (pinfunction "PC14/OSC32_3") (pintype "passive"))
      (node (ref "Y1") (pin "1") (pinfunction "OSC1_1") (pintype "passive"))
    )
    (net (code "69") (name "Net-(U1-PC15{slash}OSC32)") (class "Default")
      (node (ref "C3") (pin "2") (pintype "passive"))
      (node (ref "U1") (pin "4") (pinfunction "PC15/OSC32_4") (pintype "passive"))
      (node (ref "Y1") (pin "2") (pinfunction "OSC2_2") (pintype "passive"))
    )
    (net (code "70") (name "Net-(U1-PD0{slash}OSCIN)") (class "Default")
      (node (ref "C4") (pin "2") (pintype "passive"))
      (node (ref "R1") (pin "1") (pintype "passive"))
      (node (ref "U1") (pin "5") (pinfunction "PD0/OSCIN_5") (pintype "passive"))
      (node (ref "Y2") (pin "1") (pinfunction "OSC1_1") (pintype "passive"))
    )
    (net (code "71") (name "Net-(U1-PD1{slash}OSCOUT)") (class "Default")
      (node (ref "C5") (pin "2") (pintype "passive"))
      (node (ref "R1") (pin "2") (pintype "passive"))
      (node (ref "U1") (pin "6") (pinfunction "PD1/OSCOUT_6") (pintype "passive"))
      (node (ref "Y2") (pin "2") (pinfunction "OSC2_2") (pintype "passive"))
    )
    (net (code "72") (name "Net-(U1-VBAT)") (class "Default")
      (node (ref "D1") (pin "2") (pintype "passive"))
      (node (ref "D2") (pin "2") (pintype "passive"))
      (node (ref "U1") (pin "1") (pinfunction "VBAT_1") (pintype "passive"))
    )
    (net (code "73") (name "Net-(U1-VDDA)") (class "Default")
      (node (ref "C6") (pin "2") (pintype "passive"))
      (node (ref "C7") (pin "2") (pintype "passive"))
      (node (ref "R2") (pin "2") (pintype "passive"))
      (node (ref "U1") (pin "13") (pinfunction "VDDA_13") (pintype "passive"))
    )
    (net (code "74") (name "Net-(U2-DTR_N)") (class "Default")
      (node (ref "R15") (pin "1") (pintype "passive"))
      (node (ref "R16") (pin "1") (pintype "passive"))
      (node (ref "U2") (pin "2") (pinfunction "DTR_N_2") (pintype "passive"))
    )
    (net (code "75") (name "Net-(U2-OSC1)") (class "Default")
      (node (ref "C19") (pin "2") (pintype "passive"))
      (node (ref "U2") (pin "27") (pinfunction "OSC1_27") (pintype "passive"))
      (node (ref "Y3") (pin "1") (pinfunction "OSC1_1") (pintype "passive"))
    )
    (net (code "76") (name "Net-(U2-OSC2)") (class "Default")
      (node (ref "C20") (pin "2") (pintype "passive"))
      (node (ref "U2") (pin "28") (pinfunction "OSC2_28") (pintype "passive"))
      (node (ref "Y3") (pin "2") (pinfunction "OSC2_2") (pintype "passive"))
    )
    (net (code "77") (name "Net-(USB_1-D+)") (class "Default")
      (node (ref "R21") (pin "2") (pintype "passive"))
      (node (ref "R22") (pin "2") (pintype "passive"))
      (node (ref "USB_1") (pin "3") (pinfunction "D+_3") (pintype "passive"))
    )
    (net (code "78") (name "Net-(USB_1-D-)") (class "Default")
      (node (ref "R20") (pin "2") (pintype "passive"))
      (node (ref "USB_1") (pin "2") (pinfunction "D-_2") (pintype "passive"))
    )
    (net (code "79") (name "Net-(USB_1-GND)") (class "Default")
      (node (ref "F1") (pin "2") (pintype "passive"))
      (node (ref "USB_1") (pin "5") (pinfunction "GND_5") (pintype "passive"))
      (node (ref "USB_2") (pin "5") (pinfunction "GND_5") (pintype "passive"))
    )
    (net (code "80") (name "Net-(USB_1-VCC)") (class "Default")
      (node (ref "K1") (pin "3") (pinfunction "I/O1_3") (pintype "passive"))
      (node (ref "K1") (pin "4") (pinfunction "I/O2_4") (pintype "passive"))
      (node (ref "USB_1") (pin "1") (pinfunction "VCC_1") (pintype "passive"))
      (node (ref "USB_2") (pin "1") (pinfunction "VCC_1") (pintype "passive"))
    )
    (net (code "81") (name "Net-(USB_2-D+)") (class "Default")
      (node (ref "R24") (pin "2") (pintype "passive"))
      (node (ref "R25") (pin "2") (pintype "passive"))
      (node (ref "USB_2") (pin "3") (pinfunction "D+_3") (pintype "passive"))
    )
    (net (code "82") (name "Net-(USB_2-D-)") (class "Default")
      (node (ref "R23") (pin "2") (pintype "passive"))
      (node (ref "USB_2") (pin "2") (pinfunction "D-_2") (pintype "passive"))
    )
    (net (code "83") (name "VCC3.3") (class "Default")
      (node (ref "2.4'/2.8'LCD") (pin "24") (pinfunction "VDD3.3_24") (pintype "passive"))
      (node (ref "2.4'/2.8'LCD") (pin "25") (pinfunction "VDD3.3_25") (pintype "passive"))
      (node (ref "BOOT") (pin "1") (pinfunction "1_1") (pintype "passive"))
      (node (ref "BOOT") (pin "2") (pinfunction "2_2") (pintype "passive"))
      (node (ref "BlueTooth") (pin "5") (pinfunction "5_5") (pintype "passive"))
      (node (ref "C10") (pin "1") (pintype "passive"))
      (node (ref "C11") (pin "1") (pintype "passive"))
      (node (ref "C12") (pin "1") (pintype "passive"))
      (node (ref "C13") (pin "2") (pintype "passive"))
      (node (ref "C16") (pin "2") (pintype "passive"))
      (node (ref "C22") (pin "1") (pinfunction "VCC_1") (pintype "passive"))
      (node (ref "C24") (pin "2") (pintype "passive"))
      (node (ref "C8") (pin "1") (pintype "passive"))
      (node (ref "C9") (pin "1") (pintype "passive"))
      (node (ref "D1") (pin "1") (pintype "passive"))
      (node (ref "D4") (pin "2") (pintype "passive"))
      (node (ref "ECG") (pin "2") (pinfunction "2_2") (pintype "passive"))
      (node (ref "MLX90614") (pin "3") (pinfunction "Vdd_3") (pintype "passive"))
      (node (ref "OLED") (pin "2") (pinfunction "2_2") (pintype "passive"))
      (node (ref "P1") (pin "1") (pinfunction "1_1") (pintype "passive"))
      (node (ref "Pulse") (pin "2") (pinfunction "2_2") (pintype "passive"))
      (node (ref "Q2") (pin "1") (pinfunction "E_1") (pintype "passive"))
      (node (ref "R10") (pin "2") (pintype "passive"))
      (node (ref "R14") (pin "1") (pintype "passive"))
      (node (ref "R15") (pin "2") (pintype "passive"))
      (node (ref "R17") (pin "2") (pintype "passive"))
      (node (ref "R2") (pin "1") (pintype "passive"))
      (node (ref "R22") (pin "1") (pintype "passive"))
      (node (ref "R25") (pin "1") (pintype "passive"))
      (node (ref "R27") (pin "2") (pintype "passive"))
      (node (ref "R28") (pin "2") (pintype "passive"))
      (node (ref "R3") (pin "2") (pintype "passive"))
      (node (ref "R9") (pin "2") (pintype "passive"))
      (node (ref "U1") (pin "19") (pinfunction "VDD_19") (pintype "passive"))
      (node (ref "U1") (pin "32") (pinfunction "VDD_32") (pintype "passive"))
      (node (ref "U1") (pin "48") (pinfunction "VDD_48") (pintype "passive"))
      (node (ref "U1") (pin "64") (pinfunction "VDD_64") (pintype "passive"))
      (node (ref "U3") (pin "2") (pinfunction "OUT_2") (pintype "passive"))
      (node (ref "U3") (pin "4") (pinfunction "OUT_4") (pintype "passive"))
      (node (ref "VOUT2") (pin "2") (pinfunction "2_2") (pintype "passive"))
      (node (ref "VOUT2") (pin "4") (pinfunction "4_4") (pintype "passive"))
      (node (ref "VOUT2") (pin "6") (pinfunction "6_6") (pintype "passive"))
    )
    (net (code "84") (name "VCC5") (class "Default")
      (node (ref "2.4'/2.8'LCD") (pin "28") (pinfunction "BL_VDD_28") (pintype "passive"))
      (node (ref "C14") (pin "2") (pintype "passive"))
      (node (ref "C18") (pin "1") (pintype "passive"))
      (node (ref "C23") (pin "1") (pinfunction "VCC_1") (pintype "passive"))
      (node (ref "C25") (pin "2") (pintype "passive"))
      (node (ref "D5") (pin "2") (pintype "passive"))
      (node (ref "K1") (pin "2") (pinfunction "TAP1_2") (pintype "passive"))
      (node (ref "K1") (pin "5") (pinfunction "TAP2_5") (pintype "passive"))
      (node (ref "U2") (pin "19") (pinfunction "RESET_19") (pintype "passive"))
      (node (ref "U2") (pin "20") (pinfunction "VDD_20") (pintype "passive"))
      (node (ref "U2") (pin "22") (pinfunction "TRI_MODE_22") (pintype "passive"))
      (node (ref "U2") (pin "23") (pinfunction "LD_MODE_23") (pintype "passive"))
      (node (ref "U2") (pin "24") (pinfunction "VDD_PLL_24") (pintype "passive"))
      (node (ref "U2") (pin "8") (pinfunction "VDD_8") (pintype "passive"))
      (node (ref "U3") (pin "3") (pinfunction "IN_3") (pintype "passive"))
      (node (ref "VOUT3") (pin "2") (pinfunction "2_2") (pintype "passive"))
      (node (ref "VOUT3") (pin "4") (pinfunction "4_4") (pintype "passive"))
      (node (ref "VOUT3") (pin "6") (pinfunction "6_6") (pintype "passive"))
    )
    (net (code "85") (name "unconnected-(2.4'/2.8'LCD-MO-Pad32)") (class "Default")
      (node (ref "2.4'/2.8'LCD") (pin "32") (pinfunction "MO_32") (pintype "passive"))
    )
    (net (code "86") (name "unconnected-(BlueTooth-Pad1)") (class "Default")
      (node (ref "BlueTooth") (pin "1") (pinfunction "1_1") (pintype "passive"))
    )
    (net (code "87") (name "unconnected-(BlueTooth-Pad6)") (class "Default")
      (node (ref "BlueTooth") (pin "6") (pinfunction "6_6") (pintype "passive"))
    )
    (net (code "88") (name "unconnected-(ECG-Pad3)") (class "Default")
      (node (ref "ECG") (pin "3") (pinfunction "3_3") (pintype "passive"))
    )
    (net (code "89") (name "unconnected-(ECG-Pad4)") (class "Default")
      (node (ref "ECG") (pin "4") (pinfunction "4_4") (pintype "passive"))
    )
    (net (code "90") (name "unconnected-(K1-I{slash}O1-Pad1)") (class "Default")
      (node (ref "K1") (pin "1") (pinfunction "I/O1_1") (pintype "passive"))
    )
    (net (code "91") (name "unconnected-(K1-I{slash}O2-Pad6)") (class "Default")
      (node (ref "K1") (pin "6") (pinfunction "I/O2_6") (pintype "passive"))
    )
    (net (code "92") (name "unconnected-(PA Header-Pad1)") (class "Default")
      (node (ref "PA Header") (pin "1") (pinfunction "1_1") (pintype "passive"))
    )
    (net (code "93") (name "unconnected-(PA Header-Pad2)") (class "Default")
      (node (ref "PA Header") (pin "2") (pinfunction "2_2") (pintype "passive"))
    )
    (net (code "94") (name "unconnected-(PA Header-Pad3)") (class "Default")
      (node (ref "PA Header") (pin "3") (pinfunction "3_3") (pintype "passive"))
    )
    (net (code "95") (name "unconnected-(PA Header-Pad4)") (class "Default")
      (node (ref "PA Header") (pin "4") (pinfunction "4_4") (pintype "passive"))
    )
    (net (code "96") (name "unconnected-(PA Header-Pad5)") (class "Default")
      (node (ref "PA Header") (pin "5") (pinfunction "5_5") (pintype "passive"))
    )
    (net (code "97") (name "unconnected-(PA Header-Pad6)") (class "Default")
      (node (ref "PA Header") (pin "6") (pinfunction "6_6") (pintype "passive"))
    )
    (net (code "98") (name "unconnected-(PA Header-Pad7)") (class "Default")
      (node (ref "PA Header") (pin "7") (pinfunction "7_7") (pintype "passive"))
    )
    (net (code "99") (name "unconnected-(PA Header-Pad8)") (class "Default")
      (node (ref "PA Header") (pin "8") (pinfunction "8_8") (pintype "passive"))
    )
    (net (code "100") (name "unconnected-(PA Header-Pad9)") (class "Default")
      (node (ref "PA Header") (pin "9") (pinfunction "9_9") (pintype "passive"))
    )
    (net (code "101") (name "unconnected-(PA Header-Pad12)") (class "Default")
      (node (ref "PA Header") (pin "12") (pinfunction "12_12") (pintype "passive"))
    )
    (net (code "102") (name "unconnected-(PA Header-Pad13)") (class "Default")
      (node (ref "PA Header") (pin "13") (pinfunction "13_13") (pintype "passive"))
    )
    (net (code "103") (name "unconnected-(PA Header-Pad15)") (class "Default")
      (node (ref "PA Header") (pin "15") (pinfunction "15_15") (pintype "passive"))
    )
    (net (code "104") (name "unconnected-(PA Header-Pad16)") (class "Default")
      (node (ref "PA Header") (pin "16") (pinfunction "16_16") (pintype "passive"))
    )
    (net (code "105") (name "unconnected-(U2-CTS_N-Pad11)") (class "Default")
      (node (ref "U2") (pin "11") (pinfunction "CTS_N_11") (pintype "passive"))
    )
    (net (code "106") (name "unconnected-(U2-DCD_N-Pad10)") (class "Default")
      (node (ref "U2") (pin "10") (pinfunction "DCD_N_10") (pintype "passive"))
    )
    (net (code "107") (name "unconnected-(U2-DSR_N-Pad9)") (class "Default")
      (node (ref "U2") (pin "9") (pinfunction "DSR_N_9") (pintype "passive"))
    )
    (net (code "108") (name "unconnected-(U2-EE_CLK-Pad13)") (class "Default")
      (node (ref "U2") (pin "13") (pinfunction "EE_CLK_13") (pintype "passive"))
    )
    (net (code "109") (name "unconnected-(U2-EE_DATA-Pad14)") (class "Default")
      (node (ref "U2") (pin "14") (pinfunction "EE_DATA_14") (pintype "passive"))
    )
    (net (code "110") (name "unconnected-(U2-RI_N-Pad6)") (class "Default")
      (node (ref "U2") (pin "6") (pinfunction "RI_N_6") (pintype "passive"))
    )
    (net (code "111") (name "unconnected-(U2-SHTD_N-Pad12)") (class "Default")
      (node (ref "U2") (pin "12") (pinfunction "SHTD_N_12") (pintype "passive"))
    )
    (net (code "112") (name "unconnected-(USB_1-NC-Pad4)") (class "Default")
      (node (ref "USB_1") (pin "4") (pinfunction "NC_4") (pintype "passive"))
    )
    (net (code "113") (name "unconnected-(USB_2-NC-Pad4)") (class "Default")
      (node (ref "USB_2") (pin "4") (pinfunction "NC_4") (pintype "passive"))
    )
  )
)
